# ProProject_BM3451__2024-07-04.net
KiCad netlist of a schematic drawn in EasyEDA Pro
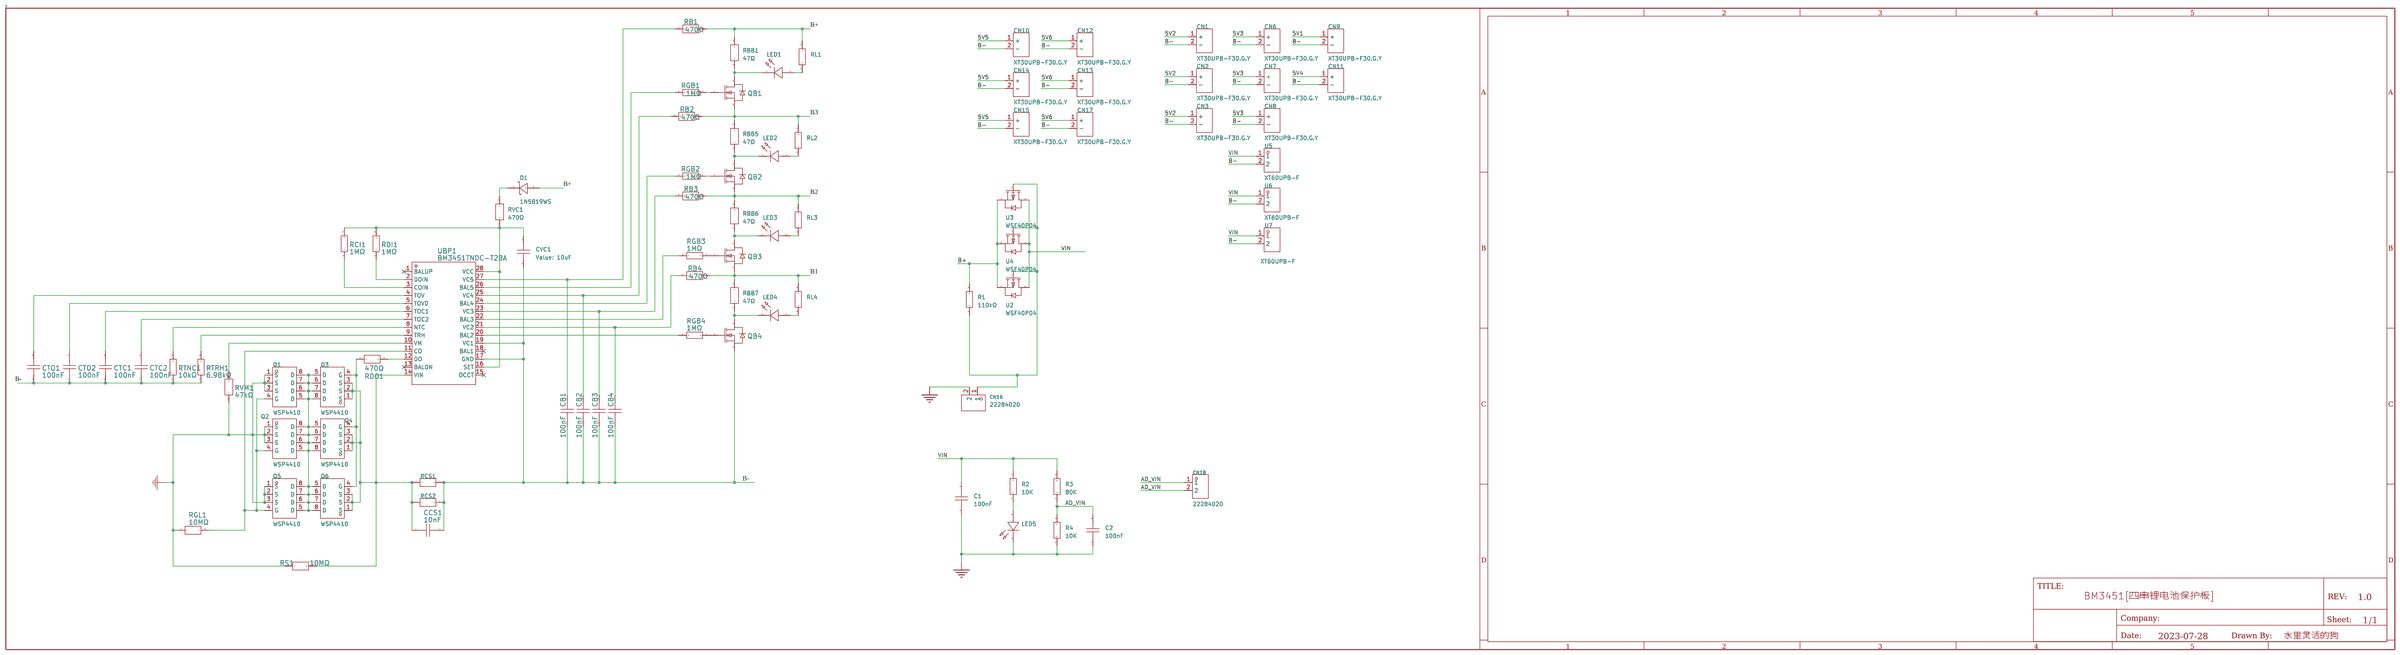
[diagram p0: schematic sheet]

(export (version "E")
  (design (tool "Eeschema 10.0.6"))
  (components
    (comp (ref "C1")
      (value "100nF")
      (footprint "easyedapro:C0603")
      (libsource (lib "easyedapro") (part "CapAcitance"))
    )
    (comp (ref "C2")
      (value "100nF")
      (footprint "easyedapro:C0603")
      (libsource (lib "easyedapro") (part "CapAcitance"))
    )
    (comp (ref "CB1")
      (value "100nF")
      (fields
        (field (name "Manufacturer Part") "GRM155R71H104KE14D")
        (field (name "Manufacturer") "muRata(村田)")
      )
      (libsource (lib "easyedapro") (part "100nF"))
    )
    (comp (ref "CB2")
      (value "100nF")
      (fields
        (field (name "Manufacturer Part") "GRM155R71H104KE14D")
        (field (name "Manufacturer") "muRata(村田)")
      )
      (libsource (lib "easyedapro") (part "100nF"))
    )
    (comp (ref "CB3")
      (value "100nF")
      (fields
        (field (name "Manufacturer Part") "GRM155R71H104KE14D")
        (field (name "Manufacturer") "muRata(村田)")
      )
      (libsource (lib "easyedapro") (part "100nF"))
    )
    (comp (ref "CB4")
      (value "100nF")
      (fields
        (field (name "Manufacturer Part") "GRM155R71H104KE14D")
        (field (name "Manufacturer") "muRata(村田)")
      )
      (libsource (lib "easyedapro") (part "100nF"))
    )
    (comp (ref "CCS1")
      (value "10nF")
      (fields
        (field (name "Manufacturer Part") "C0402C103K4RECAUTO")
        (field (name "Manufacturer") "KEMET(基美)")
      )
      (libsource (lib "easyedapro") (part "10nF"))
    )
    (comp (ref "CN1")
      (value "XT30UPB-F30.G.Y")
      (footprint "easyedapro:CONN-TH_XT30UPB-F")
      (description "类别:-;类型1:-;")
      (fields (field (name "Manufacturer") "AMASS(艾迈斯)"))
      (libsource (lib "easyedapro") (part "XT30UPB-F"))
    )
    (comp (ref "CN2")
      (value "XT30UPB-F30.G.Y")
      (footprint "easyedapro:CONN-TH_XT30UPB-F")
      (description "类别:-;类型1:-;")
      (fields (field (name "Manufacturer") "AMASS(艾迈斯)"))
      (libsource (lib "easyedapro") (part "XT30UPB-F"))
    )
    (comp (ref "CN3")
      (value "XT30UPB-F30.G.Y")
      (footprint "easyedapro:CONN-TH_XT30UPB-F")
      (description "类别:-;类型1:-;")
      (fields (field (name "Manufacturer") "AMASS(艾迈斯)"))
      (libsource (lib "easyedapro") (part "XT30UPB-F"))
    )
    (comp (ref "CN6")
      (value "XT30UPB-F30.G.Y")
      (footprint "easyedapro:CONN-TH_XT30UPB-F")
      (description "类别:-;类型1:-;")
      (fields (field (name "Manufacturer") "AMASS(艾迈斯)"))
      (libsource (lib "easyedapro") (part "XT30UPB-F"))
    )
    (comp (ref "CN7")
      (value "XT30UPB-F30.G.Y")
      (footprint "easyedapro:CONN-TH_XT30UPB-F")
      (description "类别:-;类型1:-;")
      (fields (field (name "Manufacturer") "AMASS(艾迈斯)"))
      (libsource (lib "easyedapro") (part "XT30UPB-F"))
    )
    (comp (ref "CN8")
      (value "XT30UPB-F30.G.Y")
      (footprint "easyedapro:CONN-TH_XT30UPB-F")
      (description "类别:-;类型1:-;")
      (fields (field (name "Manufacturer") "AMASS(艾迈斯)"))
      (libsource (lib "easyedapro") (part "XT30UPB-F"))
    )
    (comp (ref "CN9")
      (value "XT30UPB-F30.G.Y")
      (footprint "easyedapro:CONN-TH_XT30UPB-F")
      (description "类别:-;类型1:-;")
      (fields (field (name "Manufacturer") "AMASS(艾迈斯)"))
      (libsource (lib "easyedapro") (part "XT30UPB-F"))
    )
    (comp (ref "CN10")
      (value "XT30UPB-F30.G.Y")
      (footprint "easyedapro:CONN-TH_XT30UPB-F")
      (description "类别:-;类型1:-;")
      (fields (field (name "Manufacturer") "AMASS(艾迈斯)"))
      (libsource (lib "easyedapro") (part "XT30UPB-F"))
    )
    (comp (ref "CN11")
      (value "XT30UPB-F30.G.Y")
      (footprint "easyedapro:CONN-TH_XT30UPB-F")
      (description "类别:-;类型1:-;")
      (fields (field (name "Manufacturer") "AMASS(艾迈斯)"))
      (libsource (lib "easyedapro") (part "XT30UPB-F"))
    )
    (comp (ref "CN12")
      (value "XT30UPB-F30.G.Y")
      (footprint "easyedapro:CONN-TH_XT30UPB-F")
      (description "类别:-;类型1:-;")
      (fields (field (name "Manufacturer") "AMASS(艾迈斯)"))
      (libsource (lib "easyedapro") (part "XT30UPB-F"))
    )
    (comp (ref "CN13")
      (value "XT30UPB-F30.G.Y")
      (footprint "easyedapro:CONN-TH_XT30UPB-F")
      (description "类别:-;类型1:-;")
      (fields (field (name "Manufacturer") "AMASS(艾迈斯)"))
      (libsource (lib "easyedapro") (part "XT30UPB-F"))
    )
    (comp (ref "CN14")
      (value "XT30UPB-F30.G.Y")
      (footprint "easyedapro:CONN-TH_XT30UPB-F")
      (description "类别:-;类型1:-;")
      (fields (field (name "Manufacturer") "AMASS(艾迈斯)"))
      (libsource (lib "easyedapro") (part "XT30UPB-F"))
    )
    (comp (ref "CN15")
      (value "XT30UPB-F30.G.Y")
      (footprint "easyedapro:CONN-TH_XT30UPB-F")
      (description "类别:-;类型1:-;")
      (fields (field (name "Manufacturer") "AMASS(艾迈斯)"))
      (libsource (lib "easyedapro") (part "XT30UPB-F"))
    )
    (comp (ref "CN16")
      (value "22284020")
      (footprint "easyedapro:HDR-TH_2P-P2.54-V-M-1")
      (fields (field (name "Manufacturer") "MOLEX"))
      (libsource (lib "easyedapro") (part "22-28-4020"))
    )
    (comp (ref "CN17")
      (value "XT30UPB-F30.G.Y")
      (footprint "easyedapro:CONN-TH_XT30UPB-F")
      (description "类别:-;类型1:-;")
      (fields (field (name "Manufacturer") "AMASS(艾迈斯)"))
      (libsource (lib "easyedapro") (part "XT30UPB-F"))
    )
    (comp (ref "CN18")
      (value "22284020")
      (footprint "easyedapro:HDR-TH_2P-P2.54-V-M-1")
      (fields (field (name "Manufacturer") "MOLEX"))
      (libsource (lib "easyedapro") (part "22-28-4020"))
    )
    (comp (ref "CTC1")
      (value "100nF")
      (fields
        (field (name "Manufacturer Part") "GRM155R71H104KE14D")
        (field (name "Manufacturer") "muRata(村田)")
      )
      (libsource (lib "easyedapro") (part "100nF"))
    )
    (comp (ref "CTC2")
      (value "100nF")
      (fields
        (field (name "Manufacturer Part") "GRM155R71H104KE14D")
        (field (name "Manufacturer") "muRata(村田)")
      )
      (libsource (lib "easyedapro") (part "100nF"))
    )
    (comp (ref "CTO1")
      (value "100nF")
      (fields
        (field (name "Manufacturer Part") "GRM155R71H104KE14D")
        (field (name "Manufacturer") "muRata(村田)")
      )
      (libsource (lib "easyedapro") (part "100nF"))
    )
    (comp (ref "CTO2")
      (value "100nF")
      (fields
        (field (name "Manufacturer Part") "GRM155R71H104KE14D")
        (field (name "Manufacturer") "muRata(村田)")
      )
      (libsource (lib "easyedapro") (part "100nF"))
    )
    (comp (ref "CVC1")
      (value "10uF")
      (footprint "easyedapro:C0603")
      (description "容值:10uF;精度:±10%;额定电压:25V;材质(温度系数):X5R;")
      (fields
        (field (name "Manufacturer Part") "GRM188R61E106KA73D")
        (field (name "Manufacturer") "muRata(村田)")
      )
      (libsource (lib "easyedapro") (part "GRM188R61E106KA73D"))
    )
    (comp (ref "D1")
      (value "1N5819WS")
      (footprint "easyedapro:SOD-323_L1.8-W1.3-LS2.5-RD")
      (description "正向压降(Vf):600mV@1A;直流反向耐压(Vr):40V;平均整流电流(Io):1A;")
      (fields (field (name "Manufacturer") "Hottech(合科泰)"))
      (libsource (lib "easyedapro") (part "1N5819WS"))
    )
    (comp (ref "LED1")
      (value "XL-1005UGC")
      (footprint "easyedapro:LED0402-RD_GREEN")
      (description "发光颜色:翠绿;主波长:516nm;色温:-;功率:80mW;安装方式:正贴;")
      (fields (field (name "Manufacturer") "XINGLIGHT(成兴光)"))
      (libsource (lib "easyedapro") (part "XL-1005UGC_C2856703"))
    )
    (comp (ref "LED2")
      (value "XL-1005UGC")
      (footprint "easyedapro:LED0402-RD_GREEN")
      (description "发光颜色:翠绿;主波长:516nm;色温:-;功率:80mW;安装方式:正贴;")
      (fields (field (name "Manufacturer") "XINGLIGHT(成兴光)"))
      (libsource (lib "easyedapro") (part "XL-1005UGC_C2856703"))
    )
    (comp (ref "LED3")
      (value "XL-1005UGC")
      (footprint "easyedapro:LED0402-RD_GREEN")
      (description "发光颜色:翠绿;主波长:516nm;色温:-;功率:80mW;安装方式:正贴;")
      (fields (field (name "Manufacturer") "XINGLIGHT(成兴光)"))
      (libsource (lib "easyedapro") (part "XL-1005UGC_C2856703"))
    )
    (comp (ref "LED4")
      (value "XL-1005UGC")
      (footprint "easyedapro:LED0402-RD_GREEN")
      (description "发光颜色:翠绿;主波长:516nm;色温:-;功率:80mW;安装方式:正贴;")
      (fields (field (name "Manufacturer") "XINGLIGHT(成兴光)"))
      (libsource (lib "easyedapro") (part "XL-1005UGC_C2856703"))
    )
    (comp (ref "LED5")
      (value "XL-1005UGC")
      (footprint "easyedapro:LED0402-RD_GREEN")
      (description "发光颜色:翠绿;主波长:516nm;色温:-;功率:80mW;安装方式:正贴;")
      (fields (field (name "Manufacturer") "XINGLIGHT(成兴光)"))
      (libsource (lib "easyedapro") (part "XL-1005UGC_C2856703"))
    )
    (comp (ref "Q1")
      (value "WSP4410")
      (footprint "easyedapro:SOIC-8_L4.9-W3.9-P1.27-LS6.0-BL")
      (fields (field (name "Manufacturer") "WINSOK(微硕)"))
      (libsource (lib "easyedapro") (part "WSP4410"))
    )
    (comp (ref "Q2")
      (value "WSP4410")
      (footprint "easyedapro:SOIC-8_L4.9-W3.9-P1.27-LS6.0-BL")
      (fields (field (name "Manufacturer") "WINSOK(微硕)"))
      (libsource (lib "easyedapro") (part "WSP4410"))
    )
    (comp (ref "Q3")
      (value "WSP4410")
      (footprint "easyedapro:SOIC-8_L4.9-W3.9-P1.27-LS6.0-BL")
      (fields (field (name "Manufacturer") "WINSOK(微硕)"))
      (libsource (lib "easyedapro") (part "WSP4410"))
    )
    (comp (ref "Q4")
      (value "WSP4410")
      (footprint "easyedapro:SOIC-8_L4.9-W3.9-P1.27-LS6.0-BL")
      (fields (field (name "Manufacturer") "WINSOK(微硕)"))
      (libsource (lib "easyedapro") (part "WSP4410"))
    )
    (comp (ref "Q5")
      (value "WSP4410")
      (footprint "easyedapro:SOIC-8_L4.9-W3.9-P1.27-LS6.0-BL")
      (fields (field (name "Manufacturer") "WINSOK(微硕)"))
      (libsource (lib "easyedapro") (part "WSP4410"))
    )
    (comp (ref "Q6")
      (value "WSP4410")
      (footprint "easyedapro:SOIC-8_L4.9-W3.9-P1.27-LS6.0-BL")
      (fields (field (name "Manufacturer") "WINSOK(微硕)"))
      (libsource (lib "easyedapro") (part "WSP4410"))
    )
    (comp (ref "QB1")
      (value "2N7002")
      (fields (field (name "Manufacturer") "CJ(江苏长电/长晶)"))
      (libsource (lib "easyedapro") (part "2N7002"))
    )
    (comp (ref "QB2")
      (value "2N7002")
      (fields (field (name "Manufacturer") "CJ(江苏长电/长晶)"))
      (libsource (lib "easyedapro") (part "2N7002"))
    )
    (comp (ref "QB3")
      (value "2N7002")
      (fields (field (name "Manufacturer") "CJ(江苏长电/长晶)"))
      (libsource (lib "easyedapro") (part "2N7002"))
    )
    (comp (ref "QB4")
      (value "2N7002")
      (fields (field (name "Manufacturer") "CJ(江苏长电/长晶)"))
      (libsource (lib "easyedapro") (part "2N7002"))
    )
    (comp (ref "R1")
      (value "110kΩ")
      (footprint "easyedapro:R0805")
      (description "电阻类型:厚膜电阻;阻值:5.6kΩ;精度:±1%;功率:125mW;最大工作电压:150V;温度系数:±100ppm/°C;")
      (fields
        (field (name "Manufacturer Part") "0805W8F5601T5E")
        (field (name "Manufacturer") "UNI-ROYAL(厚声)")
      )
      (libsource (lib "easyedapro") (part "0805W8F5601T5E"))
    )
    (comp (ref "R2") (value "10K") (footprint "easyedapro:R0603") (libsource (lib "easyedapro") (part "电阻")))
    (comp (ref "R3") (value "80K") (footprint "easyedapro:R0603") (libsource (lib "easyedapro") (part "电阻")))
    (comp (ref "R4") (value "10K") (footprint "easyedapro:R0603") (libsource (lib "easyedapro") (part "电阻")))
    (comp (ref "RB1")
      (value "470Ω")
      (fields (field (name "Manufacturer Part") "AC0402FR-07470RL") (field (name "Manufacturer") "YAGEO(国巨)"))
      (libsource (lib "easyedapro") (part "470"))
    )
    (comp (ref "RB2")
      (value "470Ω")
      (fields (field (name "Manufacturer Part") "AC0402FR-07470RL") (field (name "Manufacturer") "YAGEO(国巨)"))
      (libsource (lib "easyedapro") (part "470"))
    )
    (comp (ref "RB3")
      (value "470Ω")
      (fields (field (name "Manufacturer Part") "AC0402FR-07470RL") (field (name "Manufacturer") "YAGEO(国巨)"))
      (libsource (lib "easyedapro") (part "470"))
    )
    (comp (ref "RB4")
      (value "470Ω")
      (fields (field (name "Manufacturer Part") "AC0402FR-07470RL") (field (name "Manufacturer") "YAGEO(国巨)"))
      (libsource (lib "easyedapro") (part "470"))
    )
    (comp (ref "RBB1")
      (value "47Ω")
      (footprint "easyedapro:R2512")
      (description "阻值:47Ω;精度:±1%;功率:1W;")
      (fields (field (name "Manufacturer Part") "RC-12K47R0FT") (field (name "Manufacturer") "FH(风华)"))
      (libsource (lib "easyedapro") (part "RC-12K47R0FT"))
    )
    (comp (ref "RBB5")
      (value "47Ω")
      (footprint "easyedapro:R2512")
      (description "阻值:47Ω;精度:±1%;功率:1W;")
      (fields (field (name "Manufacturer Part") "RC-12K47R0FT") (field (name "Manufacturer") "FH(风华)"))
      (libsource (lib "easyedapro") (part "RC-12K47R0FT"))
    )
    (comp (ref "RBB6")
      (value "47Ω")
      (footprint "easyedapro:R2512")
      (description "阻值:47Ω;精度:±1%;功率:1W;")
      (fields (field (name "Manufacturer Part") "RC-12K47R0FT") (field (name "Manufacturer") "FH(风华)"))
      (libsource (lib "easyedapro") (part "RC-12K47R0FT"))
    )
    (comp (ref "RBB7")
      (value "47Ω")
      (footprint "easyedapro:R2512")
      (description "阻值:47Ω;精度:±1%;功率:1W;")
      (fields (field (name "Manufacturer Part") "RC-12K47R0FT") (field (name "Manufacturer") "FH(风华)"))
      (libsource (lib "easyedapro") (part "RC-12K47R0FT"))
    )
    (comp (ref "RCI1")
      (value "1MΩ")
      (fields (field (name "Manufacturer Part") "RMC04021M1%N") (field (name "Manufacturer") "Tyohm(幸亚电阻)"))
      (libsource (lib "easyedapro") (part "1M"))
    )
    (comp (ref "RCS1")
      (value "5mΩ")
      (footprint "easyedapro:R2512")
      (description "阻值:10mΩ;精度:±1%;功率:3W;")
      (fields (field (name "Manufacturer Part") "RLP25FEGR010") (field (name "Manufacturer") "大毅科技"))
      (libsource (lib "easyedapro") (part "RLP25FEGR010"))
    )
    (comp (ref "RCS2")
      (value "5mΩ")
      (footprint "easyedapro:R2512")
      (description "阻值:10mΩ;精度:±1%;功率:3W;")
      (fields (field (name "Manufacturer Part") "RLP25FEGR010") (field (name "Manufacturer") "大毅科技"))
      (libsource (lib "easyedapro") (part "RLP25FEGR010"))
    )
    (comp (ref "RDI1")
      (value "1MΩ")
      (fields (field (name "Manufacturer Part") "RMC04021M1%N") (field (name "Manufacturer") "Tyohm(幸亚电阻)"))
      (libsource (lib "easyedapro") (part "1M"))
    )
    (comp (ref "RDO1")
      (value "470Ω")
      (fields (field (name "Manufacturer Part") "AC0402FR-07470RL") (field (name "Manufacturer") "YAGEO(国巨)"))
      (libsource (lib "easyedapro") (part "470"))
    )
    (comp (ref "RGB1")
      (value "1MΩ")
      (fields (field (name "Manufacturer Part") "RMC04021M1%N") (field (name "Manufacturer") "Tyohm(幸亚电阻)"))
      (libsource (lib "easyedapro") (part "1M"))
    )
    (comp (ref "RGB2")
      (value "1MΩ")
      (fields (field (name "Manufacturer Part") "RMC04021M1%N") (field (name "Manufacturer") "Tyohm(幸亚电阻)"))
      (libsource (lib "easyedapro") (part "1M"))
    )
    (comp (ref "RGB3")
      (value "1MΩ")
      (fields (field (name "Manufacturer Part") "RMC04021M1%N") (field (name "Manufacturer") "Tyohm(幸亚电阻)"))
      (libsource (lib "easyedapro") (part "1M"))
    )
    (comp (ref "RGB4")
      (value "1MΩ")
      (fields (field (name "Manufacturer Part") "RMC04021M1%N") (field (name "Manufacturer") "Tyohm(幸亚电阻)"))
      (libsource (lib "easyedapro") (part "1M"))
    )
    (comp (ref "RGL1")
      (value "10MΩ")
      (fields
        (field (name "Manufacturer Part") "CQ02WGF1005TCE")
        (field (name "Manufacturer") "UNI-ROYAL(厚声)")
      )
      (libsource (lib "easyedapro") (part "10M"))
    )
    (comp (ref "RL1")
      (value "100Ω")
      (footprint "easyedapro:R0402")
      (description "电阻类型:厚膜电阻;阻值:100Ω;精度:±1%;功率:62.5mW;")
      (fields
        (field (name "Manufacturer Part") "0402WGF1000TCE")
        (field (name "Manufacturer") "UNI-ROYAL(厚声)")
      )
      (libsource (lib "easyedapro") (part "0402WGF1000TCE"))
    )
    (comp (ref "RL2")
      (value "100Ω")
      (footprint "easyedapro:R0402")
      (description "电阻类型:厚膜电阻;阻值:100Ω;精度:±1%;功率:62.5mW;")
      (fields
        (field (name "Manufacturer Part") "0402WGF1000TCE")
        (field (name "Manufacturer") "UNI-ROYAL(厚声)")
      )
      (libsource (lib "easyedapro") (part "0402WGF1000TCE"))
    )
    (comp (ref "RL3")
      (value "100Ω")
      (footprint "easyedapro:R0402")
      (description "电阻类型:厚膜电阻;阻值:100Ω;精度:±1%;功率:62.5mW;")
      (fields
        (field (name "Manufacturer Part") "0402WGF1000TCE")
        (field (name "Manufacturer") "UNI-ROYAL(厚声)")
      )
      (libsource (lib "easyedapro") (part "0402WGF1000TCE"))
    )
    (comp (ref "RL4")
      (value "100Ω")
      (footprint "easyedapro:R0402")
      (description "电阻类型:厚膜电阻;阻值:100Ω;精度:±1%;功率:62.5mW;")
      (fields
        (field (name "Manufacturer Part") "0402WGF1000TCE")
        (field (name "Manufacturer") "UNI-ROYAL(厚声)")
      )
      (libsource (lib "easyedapro") (part "0402WGF1000TCE"))
    )
    (comp (ref "RS1")
      (value "10MΩ")
      (fields
        (field (name "Manufacturer Part") "CQ02WGF1005TCE")
        (field (name "Manufacturer") "UNI-ROYAL(厚声)")
      )
      (libsource (lib "easyedapro") (part "10M"))
    )
    (comp (ref "RTNC1")
      (value "10kΩ")
      (fields
        (field (name "Manufacturer Part") "HQ02WAJ0103TCE")
        (field (name "Manufacturer") "UNI-ROYAL(厚声)")
      )
      (libsource (lib "easyedapro") (part "10K"))
    )
    (comp (ref "RTRH1")
      (value "6.98kΩ")
      (fields
        (field (name "Manufacturer Part") "0402WGF6981TCE")
        (field (name "Manufacturer") "UNI-ROYAL(厚声)")
      )
      (libsource (lib "easyedapro") (part "6.98K"))
    )
    (comp (ref "RVC1")
      (value "470Ω")
      (footprint "easyedapro:R0402")
      (description "电阻类型:厚膜电阻;阻值:470Ω;精度:±1%;功率:62.5mW;")
      (fields (field (name "Manufacturer Part") "AC0402FR-07470RL") (field (name "Manufacturer") "YAGEO(国巨)"))
      (libsource (lib "easyedapro") (part "AC0402FR-07470RL"))
    )
    (comp (ref "RVM1")
      (value "47kΩ")
      (fields (field (name "Manufacturer Part") "SY0402FN47KP") (field (name "Manufacturer") "SANYEAR(叁叶源)"))
      (libsource (lib "easyedapro") (part "47K"))
    )
    (comp (ref "U2")
      (value "WSF40P04")
      (footprint "easyedapro:TO-252-3_L6.5-W5.8-P4.58-TL")
      (fields (field (name "Manufacturer") "WINSOK(微硕)"))
      (libsource (lib "easyedapro") (part "WSF40P04"))
    )
    (comp (ref "U3")
      (value "WSF40P04")
      (footprint "easyedapro:TO-252-3_L6.5-W5.8-P4.58-TL")
      (fields (field (name "Manufacturer") "WINSOK(微硕)"))
      (libsource (lib "easyedapro") (part "WSF40P04"))
    )
    (comp (ref "U4")
      (value "WSF40P04")
      (footprint "easyedapro:TO-252-3_L6.5-W5.8-P4.58-TL")
      (fields (field (name "Manufacturer") "WINSOK(微硕)"))
      (libsource (lib "easyedapro") (part "WSF40P04"))
    )
    (comp (ref "U5")
      (value "XT60UPB-F")
      (footprint "easyedapro:CONN-TH_XT60UPB-F")
      (libsource (lib "easyedapro") (part "XT60UPB-F"))
    )
    (comp (ref "U6")
      (value "XT60UPB-F")
      (footprint "easyedapro:CONN-TH_XT60UPB-F")
      (libsource (lib "easyedapro") (part "XT60UPB-F"))
    )
    (comp (ref "U7")
      (value "XT60UPB-F")
      (footprint "easyedapro:CONN-TH_XT60UPB-F")
      (libsource (lib "easyedapro") (part "XT60UPB-F"))
    )
    (comp (ref "UBP1") (value "BM3451TNDC-T28A") (libsource (lib "easyedapro") (part "BM3451-T28")))
  )
  (nets
    (net (code "1") (name "/5V1") (class "Default")
      (node (ref "CN9") (pin "1") (pinfunction "+_1") (pintype "unspecified"))
    )
    (net (code "2") (name "/5V2") (class "Default")
      (node (ref "CN1") (pin "1") (pinfunction "+_1") (pintype "unspecified"))
      (node (ref "CN2") (pin "1") (pinfunction "+_1") (pintype "unspecified"))
      (node (ref "CN3") (pin "1") (pinfunction "+_1") (pintype "unspecified"))
    )
    (net (code "3") (name "/5V3") (class "Default")
      (node (ref "CN6") (pin "1") (pinfunction "+_1") (pintype "unspecified"))
      (node (ref "CN7") (pin "1") (pinfunction "+_1") (pintype "unspecified"))
      (node (ref "CN8") (pin "1") (pinfunction "+_1") (pintype "unspecified"))
    )
    (net (code "4") (name "/5V4") (class "Default")
      (node (ref "CN11") (pin "1") (pinfunction "+_1") (pintype "unspecified"))
    )
    (net (code "5") (name "/5V5") (class "Default")
      (node (ref "CN10") (pin "1") (pinfunction "+_1") (pintype "unspecified"))
      (node (ref "CN14") (pin "1") (pinfunction "+_1") (pintype "unspecified"))
      (node (ref "CN15") (pin "1") (pinfunction "+_1") (pintype "unspecified"))
    )
    (net (code "6") (name "/5V6") (class "Default")
      (node (ref "CN12") (pin "1") (pinfunction "+_1") (pintype "unspecified"))
      (node (ref "CN13") (pin "1") (pinfunction "+_1") (pintype "unspecified"))
      (node (ref "CN17") (pin "1") (pinfunction "+_1") (pintype "unspecified"))
    )
    (net (code "7") (name "/AD_VIN") (class "Default")
      (node (ref "C2") (pin "2") (pinfunction "2_2") (pintype "input"))
      (node (ref "CN18") (pin "1") (pinfunction "1_1") (pintype "input"))
      (node (ref "CN18") (pin "2") (pinfunction "2_2") (pintype "input"))
      (node (ref "R3") (pin "1") (pinfunction "1_1") (pintype "input"))
      (node (ref "R4") (pin "2") (pinfunction "2_2") (pintype "input"))
    )
    (net (code "8") (name "/B+") (class "Default")
      (node (ref "D1") (pin "2") (pinfunction "A_2") (pintype "unspecified"))
      (node (ref "R1") (pin "2") (pinfunction "2_2") (pintype "input"))
      (node (ref "RB1") (pin "1") (pinfunction "1_1") (pintype "input"))
      (node (ref "RBB1") (pin "2") (pinfunction "2_2") (pintype "input"))
      (node (ref "RL1") (pin "2") (pinfunction "2_2") (pintype "input"))
      (node (ref "U2") (pin "3") (pinfunction "S_3") (pintype "unspecified"))
      (node (ref "U3") (pin "3") (pinfunction "S_3") (pintype "unspecified"))
      (node (ref "U4") (pin "3") (pinfunction "S_3") (pintype "unspecified"))
    )
    (net (code "9") (name "/B1") (class "Default")
      (node (ref "QB3") (pin "2") (pinfunction "S_2") (pintype "input"))
      (node (ref "RB4") (pin "1") (pinfunction "1_1") (pintype "input"))
      (node (ref "RBB7") (pin "2") (pinfunction "2_2") (pintype "input"))
      (node (ref "RL4") (pin "2") (pinfunction "2_2") (pintype "input"))
    )
    (net (code "10") (name "/B2") (class "Default")
      (node (ref "QB2") (pin "2") (pinfunction "S_2") (pintype "input"))
      (node (ref "RB3") (pin "1") (pinfunction "1_1") (pintype "input"))
      (node (ref "RBB6") (pin "2") (pinfunction "2_2") (pintype "input"))
      (node (ref "RL3") (pin "2") (pinfunction "2_2") (pintype "input"))
    )
    (net (code "11") (name "/B3") (class "Default")
      (node (ref "QB1") (pin "2") (pinfunction "S_2") (pintype "input"))
      (node (ref "RB2") (pin "1") (pinfunction "1_1") (pintype "input"))
      (node (ref "RBB5") (pin "2") (pinfunction "2_2") (pintype "input"))
      (node (ref "RL2") (pin "2") (pinfunction "2_2") (pintype "input"))
    )
    (net (code "12") (name "/VIN") (class "Default")
      (node (ref "C1") (pin "2") (pinfunction "2_2") (pintype "input"))
      (node (ref "R2") (pin "2") (pinfunction "2_2") (pintype "input"))
      (node (ref "R3") (pin "2") (pinfunction "2_2") (pintype "input"))
      (node (ref "U2") (pin "2") (pinfunction "D_2") (pintype "unspecified"))
      (node (ref "U3") (pin "2") (pinfunction "D_2") (pintype "unspecified"))
      (node (ref "U4") (pin "2") (pinfunction "D_2") (pintype "unspecified"))
      (node (ref "U5") (pin "1") (pinfunction "1_1") (pintype "input"))
      (node (ref "U6") (pin "1") (pinfunction "1_1") (pintype "input"))
      (node (ref "U7") (pin "1") (pinfunction "1_1") (pintype "input"))
    )
    (net (code "13") (name "B-") (class "Default")
      (node (ref "C1") (pin "1") (pinfunction "1_1") (pintype "input"))
      (node (ref "C2") (pin "1") (pinfunction "1_1") (pintype "input"))
      (node (ref "CB1") (pin "1") (pinfunction "1_1") (pintype "input"))
      (node (ref "CB2") (pin "1") (pinfunction "1_1") (pintype "input"))
      (node (ref "CB3") (pin "1") (pinfunction "1_1") (pintype "input"))
      (node (ref "CB4") (pin "1") (pinfunction "1_1") (pintype "input"))
      (node (ref "CCS1") (pin "2") (pinfunction "2_2") (pintype "input"))
      (node (ref "CN1") (pin "2") (pinfunction "-_2") (pintype "unspecified"))
      (node (ref "CN10") (pin "2") (pinfunction "-_2") (pintype "unspecified"))
      (node (ref "CN11") (pin "2") (pinfunction "-_2") (pintype "unspecified"))
      (node (ref "CN12") (pin "2") (pinfunction "-_2") (pintype "unspecified"))
      (node (ref "CN13") (pin "2") (pinfunction "-_2") (pintype "unspecified"))
      (node (ref "CN14") (pin "2") (pinfunction "-_2") (pintype "unspecified"))
      (node (ref "CN15") (pin "2") (pinfunction "-_2") (pintype "unspecified"))
      (node (ref "CN17") (pin "2") (pinfunction "-_2") (pintype "unspecified"))
      (node (ref "CN2") (pin "2") (pinfunction "-_2") (pintype "unspecified"))
      (node (ref "CN3") (pin "2") (pinfunction "-_2") (pintype "unspecified"))
      (node (ref "CN6") (pin "2") (pinfunction "-_2") (pintype "unspecified"))
      (node (ref "CN7") (pin "2") (pinfunction "-_2") (pintype "unspecified"))
      (node (ref "CN8") (pin "2") (pinfunction "-_2") (pintype "unspecified"))
      (node (ref "CN9") (pin "2") (pinfunction "-_2") (pintype "unspecified"))
      (node (ref "CTC1") (pin "2") (pinfunction "2_2") (pintype "input"))
      (node (ref "CTC2") (pin "1") (pinfunction "1_1") (pintype "input"))
      (node (ref "CTO1") (pin "1") (pinfunction "1_1") (pintype "input"))
      (node (ref "CTO2") (pin "1") (pinfunction "1_1") (pintype "input"))
      (node (ref "CVC1") (pin "2") (pinfunction "2_2") (pintype "input"))
      (node (ref "LED5") (pin "1") (pinfunction "K_1") (pintype "input"))
      (node (ref "QB4") (pin "2") (pinfunction "S_2") (pintype "input"))
      (node (ref "R4") (pin "1") (pinfunction "1_1") (pintype "input"))
      (node (ref "RCS1") (pin "2") (pinfunction "2_2") (pintype "input"))
      (node (ref "RCS2") (pin "2") (pinfunction "2_2") (pintype "input"))
      (node (ref "RTNC1") (pin "1") (pinfunction "1_1") (pintype "input"))
      (node (ref "RTRH1") (pin "1") (pinfunction "1_1") (pintype "input"))
      (node (ref "U5") (pin "2") (pinfunction "2_2") (pintype "input"))
      (node (ref "U6") (pin "2") (pinfunction "2_2") (pintype "input"))
      (node (ref "U7") (pin "2") (pinfunction "2_2") (pintype "input"))
      (node (ref "UBP1") (pin "17") (pinfunction "GND_17") (pintype "input"))
      (node (ref "UBP1") (pin "19") (pinfunction "VC1_19") (pintype "input"))
    )
    (net (code "14") (name "GND") (class "Default")
      (node (ref "CN16") (pin "2") (pinfunction "2_2") (pintype "input"))
      (node (ref "Q1") (pin "1") (pinfunction "S_1") (pintype "unspecified"))
      (node (ref "Q1") (pin "2") (pinfunction "S_2") (pintype "unspecified"))
      (node (ref "Q1") (pin "3") (pinfunction "S_3") (pintype "unspecified"))
      (node (ref "Q2") (pin "1") (pinfunction "S_1") (pintype "unspecified"))
      (node (ref "Q2") (pin "2") (pinfunction "S_2") (pintype "unspecified"))
      (node (ref "Q2") (pin "3") (pinfunction "S_3") (pintype "unspecified"))
      (node (ref "Q5") (pin "1") (pinfunction "S_1") (pintype "unspecified"))
      (node (ref "Q5") (pin "2") (pinfunction "S_2") (pintype "unspecified"))
      (node (ref "Q5") (pin "3") (pinfunction "S_3") (pintype "unspecified"))
      (node (ref "RGL1") (pin "1") (pinfunction "1_1") (pintype "input"))
      (node (ref "RS1") (pin "1") (pinfunction "1_1") (pintype "input"))
      (node (ref "RVM1") (pin "1") (pinfunction "1_1") (pintype "input"))
    )
    (net (code "15") (name "Net-(D1-K)") (class "Default")
      (node (ref "D1") (pin "1") (pinfunction "K_1") (pintype "unspecified"))
      (node (ref "RVC1") (pin "2") (pinfunction "2_2") (pintype "input"))
    )
    (net (code "16") (name "Net-(LED1-A)") (class "Default")
      (node (ref "LED1") (pin "2") (pinfunction "A_2") (pintype "input"))
      (node (ref "RL1") (pin "1") (pinfunction "1_1") (pintype "input"))
    )
    (net (code "17") (name "Net-(LED1-K)") (class "Default")
      (node (ref "LED1") (pin "1") (pinfunction "K_1") (pintype "input"))
      (node (ref "QB1") (pin "3") (pinfunction "D_3") (pintype "input"))
      (node (ref "RBB1") (pin "1") (pinfunction "1_1") (pintype "input"))
    )
    (net (code "18") (name "Net-(LED2-A)") (class "Default")
      (node (ref "LED2") (pin "2") (pinfunction "A_2") (pintype "input"))
      (node (ref "RL2") (pin "1") (pinfunction "1_1") (pintype "input"))
    )
    (net (code "19") (name "Net-(LED2-K)") (class "Default")
      (node (ref "LED2") (pin "1") (pinfunction "K_1") (pintype "input"))
      (node (ref "QB2") (pin "3") (pinfunction "D_3") (pintype "input"))
      (node (ref "RBB5") (pin "1") (pinfunction "1_1") (pintype "input"))
    )
    (net (code "20") (name "Net-(LED3-A)") (class "Default")
      (node (ref "LED3") (pin "2") (pinfunction "A_2") (pintype "input"))
      (node (ref "RL3") (pin "1") (pinfunction "1_1") (pintype "input"))
    )
    (net (code "21") (name "Net-(LED3-K)") (class "Default")
      (node (ref "LED3") (pin "1") (pinfunction "K_1") (pintype "input"))
      (node (ref "QB3") (pin "3") (pinfunction "D_3") (pintype "input"))
      (node (ref "RBB6") (pin "1") (pinfunction "1_1") (pintype "input"))
    )
    (net (code "22") (name "Net-(LED4-A)") (class "Default")
      (node (ref "LED4") (pin "2") (pinfunction "A_2") (pintype "input"))
      (node (ref "RL4") (pin "1") (pinfunction "1_1") (pintype "input"))
    )
    (net (code "23") (name "Net-(LED4-K)") (class "Default")
      (node (ref "LED4") (pin "1") (pinfunction "K_1") (pintype "input"))
      (node (ref "QB4") (pin "3") (pinfunction "D_3") (pintype "input"))
      (node (ref "RBB7") (pin "1") (pinfunction "1_1") (pintype "input"))
    )
    (net (code "24") (name "Net-(LED5-A)") (class "Default")
      (node (ref "LED5") (pin "2") (pinfunction "A_2") (pintype "input"))
      (node (ref "R2") (pin "1") (pinfunction "1_1") (pintype "input"))
    )
    (net (code "25") (name "Net-(Q1-D-Pad5)") (class "Default")
      (node (ref "Q1") (pin "5") (pinfunction "D_5") (pintype "unspecified"))
      (node (ref "Q1") (pin "6") (pinfunction "D_6") (pintype "unspecified"))
      (node (ref "Q1") (pin "7") (pinfunction "D_7") (pintype "unspecified"))
      (node (ref "Q1") (pin "8") (pinfunction "D_8") (pintype "unspecified"))
      (node (ref "Q2") (pin "5") (pinfunction "D_5") (pintype "unspecified"))
      (node (ref "Q2") (pin "6") (pinfunction "D_6") (pintype "unspecified"))
      (node (ref "Q2") (pin "7") (pinfunction "D_7") (pintype "unspecified"))
      (node (ref "Q2") (pin "8") (pinfunction "D_8") (pintype "unspecified"))
      (node (ref "Q3") (pin "5") (pinfunction "D_5") (pintype "unspecified"))
      (node (ref "Q3") (pin "6") (pinfunction "D_6") (pintype "unspecified"))
      (node (ref "Q3") (pin "7") (pinfunction "D_7") (pintype "unspecified"))
      (node (ref "Q3") (pin "8") (pinfunction "D_8") (pintype "unspecified"))
      (node (ref "Q4") (pin "5") (pinfunction "D_5") (pintype "unspecified"))
      (node (ref "Q4") (pin "6") (pinfunction "D_6") (pintype "unspecified"))
      (node (ref "Q4") (pin "7") (pinfunction "D_7") (pintype "unspecified"))
      (node (ref "Q4") (pin "8") (pinfunction "D_8") (pintype "unspecified"))
      (node (ref "Q5") (pin "5") (pinfunction "D_5") (pintype "unspecified"))
      (node (ref "Q5") (pin "6") (pinfunction "D_6") (pintype "unspecified"))
      (node (ref "Q5") (pin "7") (pinfunction "D_7") (pintype "unspecified"))
      (node (ref "Q5") (pin "8") (pinfunction "D_8") (pintype "unspecified"))
      (node (ref "Q6") (pin "5") (pinfunction "D_5") (pintype "unspecified"))
      (node (ref "Q6") (pin "6") (pinfunction "D_6") (pintype "unspecified"))
      (node (ref "Q6") (pin "7") (pinfunction "D_7") (pintype "unspecified"))
      (node (ref "Q6") (pin "8") (pinfunction "D_8") (pintype "unspecified"))
    )
    (net (code "26") (name "Net-(Q1-G)") (class "Default")
      (node (ref "Q1") (pin "4") (pinfunction "G_4") (pintype "unspecified"))
      (node (ref "Q2") (pin "4") (pinfunction "G_4") (pintype "unspecified"))
      (node (ref "Q5") (pin "4") (pinfunction "G_4") (pintype "unspecified"))
      (node (ref "RGL1") (pin "2") (pinfunction "2_2") (pintype "input"))
      (node (ref "UBP1") (pin "11") (pinfunction "CO_11") (pintype "input"))
    )
    (net (code "27") (name "Net-(Q3-G)") (class "Default")
      (node (ref "Q3") (pin "4") (pinfunction "G_4") (pintype "unspecified"))
      (node (ref "Q4") (pin "4") (pinfunction "G_4") (pintype "unspecified"))
      (node (ref "Q6") (pin "4") (pinfunction "G_4") (pintype "unspecified"))
      (node (ref "RDO1") (pin "2") (pinfunction "2_2") (pintype "input"))
    )
    (net (code "28") (name "Net-(QB1-G)") (class "Default")
      (node (ref "QB1") (pin "1") (pinfunction "G_1") (pintype "input"))
      (node (ref "RGB1") (pin "1") (pinfunction "1_1") (pintype "input"))
    )
    (net (code "29") (name "Net-(QB2-G)") (class "Default")
      (node (ref "QB2") (pin "1") (pinfunction "G_1") (pintype "input"))
      (node (ref "RGB2") (pin "1") (pinfunction "1_1") (pintype "input"))
    )
    (net (code "30") (name "Net-(QB3-G)") (class "Default")
      (node (ref "QB3") (pin "1") (pinfunction "G_1") (pintype "input"))
      (node (ref "RGB3") (pin "1") (pinfunction "1_1") (pintype "input"))
    )
    (net (code "31") (name "Net-(QB4-G)") (class "Default")
      (node (ref "QB4") (pin "1") (pinfunction "G_1") (pintype "input"))
      (node (ref "RGB4") (pin "1") (pinfunction "1_1") (pintype "input"))
    )
    (net (code "32") (name "Net-(U2-G)") (class "Default")
      (node (ref "CN16") (pin "1") (pinfunction "1_1") (pintype "input"))
      (node (ref "R1") (pin "1") (pinfunction "1_1") (pintype "input"))
      (node (ref "U2") (pin "1") (pinfunction "G_1") (pintype "unspecified"))
      (node (ref "U3") (pin "1") (pinfunction "G_1") (pintype "unspecified"))
      (node (ref "U4") (pin "1") (pinfunction "G_1") (pintype "unspecified"))
    )
    (net (code "33") (name "Net-(UBP1-BAL2)") (class "Default")
      (node (ref "RGB4") (pin "2") (pinfunction "2_2") (pintype "input"))
      (node (ref "UBP1") (pin "20") (pinfunction "BAL2_20") (pintype "input"))
    )
    (net (code "34") (name "Net-(UBP1-BAL3)") (class "Default")
      (node (ref "RGB3") (pin "2") (pinfunction "2_2") (pintype "input"))
      (node (ref "UBP1") (pin "22") (pinfunction "BAL3_22") (pintype "input"))
    )
    (net (code "35") (name "Net-(UBP1-BAL4)") (class "Default")
      (node (ref "RGB2") (pin "2") (pinfunction "2_2") (pintype "input"))
      (node (ref "UBP1") (pin "24") (pinfunction "BAL4_24") (pintype "input"))
    )
    (net (code "36") (name "Net-(UBP1-BAL5)") (class "Default")
      (node (ref "RGB1") (pin "2") (pinfunction "2_2") (pintype "input"))
      (node (ref "UBP1") (pin "26") (pinfunction "BAL5_26") (pintype "input"))
    )
    (net (code "37") (name "Net-(UBP1-COIN)") (class "Default")
      (node (ref "RCI1") (pin "1") (pinfunction "1_1") (pintype "input"))
      (node (ref "UBP1") (pin "3") (pinfunction "COIN_3") (pintype "input"))
    )
    (net (code "38") (name "Net-(UBP1-DO)") (class "Default")
      (node (ref "RDO1") (pin "1") (pinfunction "1_1") (pintype "input"))
      (node (ref "UBP1") (pin "12") (pinfunction "DO_12") (pintype "input"))
    )
    (net (code "39") (name "Net-(UBP1-DOIN)") (class "Default")
      (node (ref "RDI1") (pin "1") (pinfunction "1_1") (pintype "input"))
      (node (ref "UBP1") (pin "2") (pinfunction "DOIN_2") (pintype "input"))
    )
    (net (code "40") (name "Net-(UBP1-NTC)") (class "Default")
      (node (ref "RTNC1") (pin "2") (pinfunction "2_2") (pintype "input"))
      (node (ref "UBP1") (pin "8") (pinfunction "NTC_8") (pintype "input"))
    )
    (net (code "41") (name "Net-(UBP1-SET)") (class "Default")
      (node (ref "CVC1") (pin "1") (pinfunction "1_1") (pintype "input"))
      (node (ref "RCI1") (pin "2") (pinfunction "2_2") (pintype "input"))
      (node (ref "RDI1") (pin "2") (pinfunction "2_2") (pintype "input"))
      (node (ref "RVC1") (pin "1") (pinfunction "1_1") (pintype "input"))
      (node (ref "UBP1") (pin "16") (pinfunction "SET_16") (pintype "input"))
      (node (ref "UBP1") (pin "28") (pinfunction "VCC_28") (pintype "input"))
    )
    (net (code "42") (name "Net-(UBP1-TOC1)") (class "Default")
      (node (ref "CTC1") (pin "1") (pinfunction "1_1") (pintype "input"))
      (node (ref "UBP1") (pin "6") (pinfunction "TOC1_6") (pintype "input"))
    )
    (net (code "43") (name "Net-(UBP1-TOC2)") (class "Default")
      (node (ref "CTC2") (pin "2") (pinfunction "2_2") (pintype "input"))
      (node (ref "UBP1") (pin "7") (pinfunction "TOC2_7") (pintype "input"))
    )
    (net (code "44") (name "Net-(UBP1-TOV)") (class "Default")
      (node (ref "CTO1") (pin "2") (pinfunction "2_2") (pintype "input"))
      (node (ref "UBP1") (pin "4") (pinfunction "TOV_4") (pintype "input"))
    )
    (net (code "45") (name "Net-(UBP1-TOVD)") (class "Default")
      (node (ref "CTO2") (pin "2") (pinfunction "2_2") (pintype "input"))
      (node (ref "UBP1") (pin "5") (pinfunction "TOVD_5") (pintype "input"))
    )
    (net (code "46") (name "Net-(UBP1-TRH)") (class "Default")
      (node (ref "RTRH1") (pin "2") (pinfunction "2_2") (pintype "input"))
      (node (ref "UBP1") (pin "9") (pinfunction "TRH_9") (pintype "input"))
    )
    (net (code "47") (name "Net-(UBP1-VC2)") (class "Default")
      (node (ref "CB4") (pin "2") (pinfunction "2_2") (pintype "input"))
      (node (ref "RB4") (pin "2") (pinfunction "2_2") (pintype "input"))
      (node (ref "UBP1") (pin "21") (pinfunction "VC2_21") (pintype "input"))
    )
    (net (code "48") (name "Net-(UBP1-VC3)") (class "Default")
      (node (ref "CB3") (pin "2") (pinfunction "2_2") (pintype "input"))
      (node (ref "RB3") (pin "2") (pinfunction "2_2") (pintype "input"))
      (node (ref "UBP1") (pin "23") (pinfunction "VC3_23") (pintype "input"))
    )
    (net (code "49") (name "Net-(UBP1-VC4)") (class "Default")
      (node (ref "CB2") (pin "2") (pinfunction "2_2") (pintype "input"))
      (node (ref "RB2") (pin "2") (pinfunction "2_2") (pintype "input"))
      (node (ref "UBP1") (pin "25") (pinfunction "VC4_25") (pintype "input"))
    )
    (net (code "50") (name "Net-(UBP1-VC5)") (class "Default")
      (node (ref "CB1") (pin "2") (pinfunction "2_2") (pintype "input"))
      (node (ref "RB1") (pin "2") (pinfunction "2_2") (pintype "input"))
      (node (ref "UBP1") (pin "27") (pinfunction "VC5_27") (pintype "input"))
    )
    (net (code "51") (name "Net-(UBP1-VIN)") (class "Default")
      (node (ref "CCS1") (pin "1") (pinfunction "1_1") (pintype "input"))
      (node (ref "Q3") (pin "1") (pinfunction "S_1") (pintype "unspecified"))
      (node (ref "Q3") (pin "2") (pinfunction "S_2") (pintype "unspecified"))
      (node (ref "Q3") (pin "3") (pinfunction "S_3") (pintype "unspecified"))
      (node (ref "Q4") (pin "1") (pinfunction "S_1") (pintype "unspecified"))
      (node (ref "Q4") (pin "2") (pinfunction "S_2") (pintype "unspecified"))
      (node (ref "Q4") (pin "3") (pinfunction "S_3") (pintype "unspecified"))
      (node (ref "Q6") (pin "1") (pinfunction "S_1") (pintype "unspecified"))
      (node (ref "Q6") (pin "2") (pinfunction "S_2") (pintype "unspecified"))
      (node (ref "Q6") (pin "3") (pinfunction "S_3") (pintype "unspecified"))
      (node (ref "RCS1") (pin "1") (pinfunction "1_1") (pintype "input"))
      (node (ref "RCS2") (pin "1") (pinfunction "1_1") (pintype "input"))
      (node (ref "RS1") (pin "2") (pinfunction "2_2") (pintype "input"))
      (node (ref "UBP1") (pin "14") (pinfunction "VIN_14") (pintype "input"))
    )
    (net (code "52") (name "Net-(UBP1-VM)") (class "Default")
      (node (ref "RVM1") (pin "2") (pinfunction "2_2") (pintype "input"))
      (node (ref "UBP1") (pin "10") (pinfunction "VM_10") (pintype "input"))
    )
    (net (code "53") (name "unconnected-(UBP1-BAL1-Pad18)") (class "Default")
      (node (ref "UBP1") (pin "18") (pinfunction "BAL1_18") (pintype "input+no_connect"))
    )
    (net (code "54") (name "unconnected-(UBP1-BALDN-Pad13)") (class "Default")
      (node (ref "UBP1") (pin "13") (pinfunction "BALDN_13") (pintype "input+no_connect"))
    )
    (net (code "55") (name "unconnected-(UBP1-BALUP-Pad1)") (class "Default")
      (node (ref "UBP1") (pin "1") (pinfunction "BALUP_1") (pintype "input+no_connect"))
    )
    (net (code "56") (name "unconnected-(UBP1-OCCT-Pad15)") (class "Default")
      (node (ref "UBP1") (pin "15") (pinfunction "OCCT_15") (pintype "input+no_connect"))
    )
  )
)
